# Block_UART_I2C_CAN_and_GPIOs.net
KiCad netlist of a schematic drawn in Altium Designer
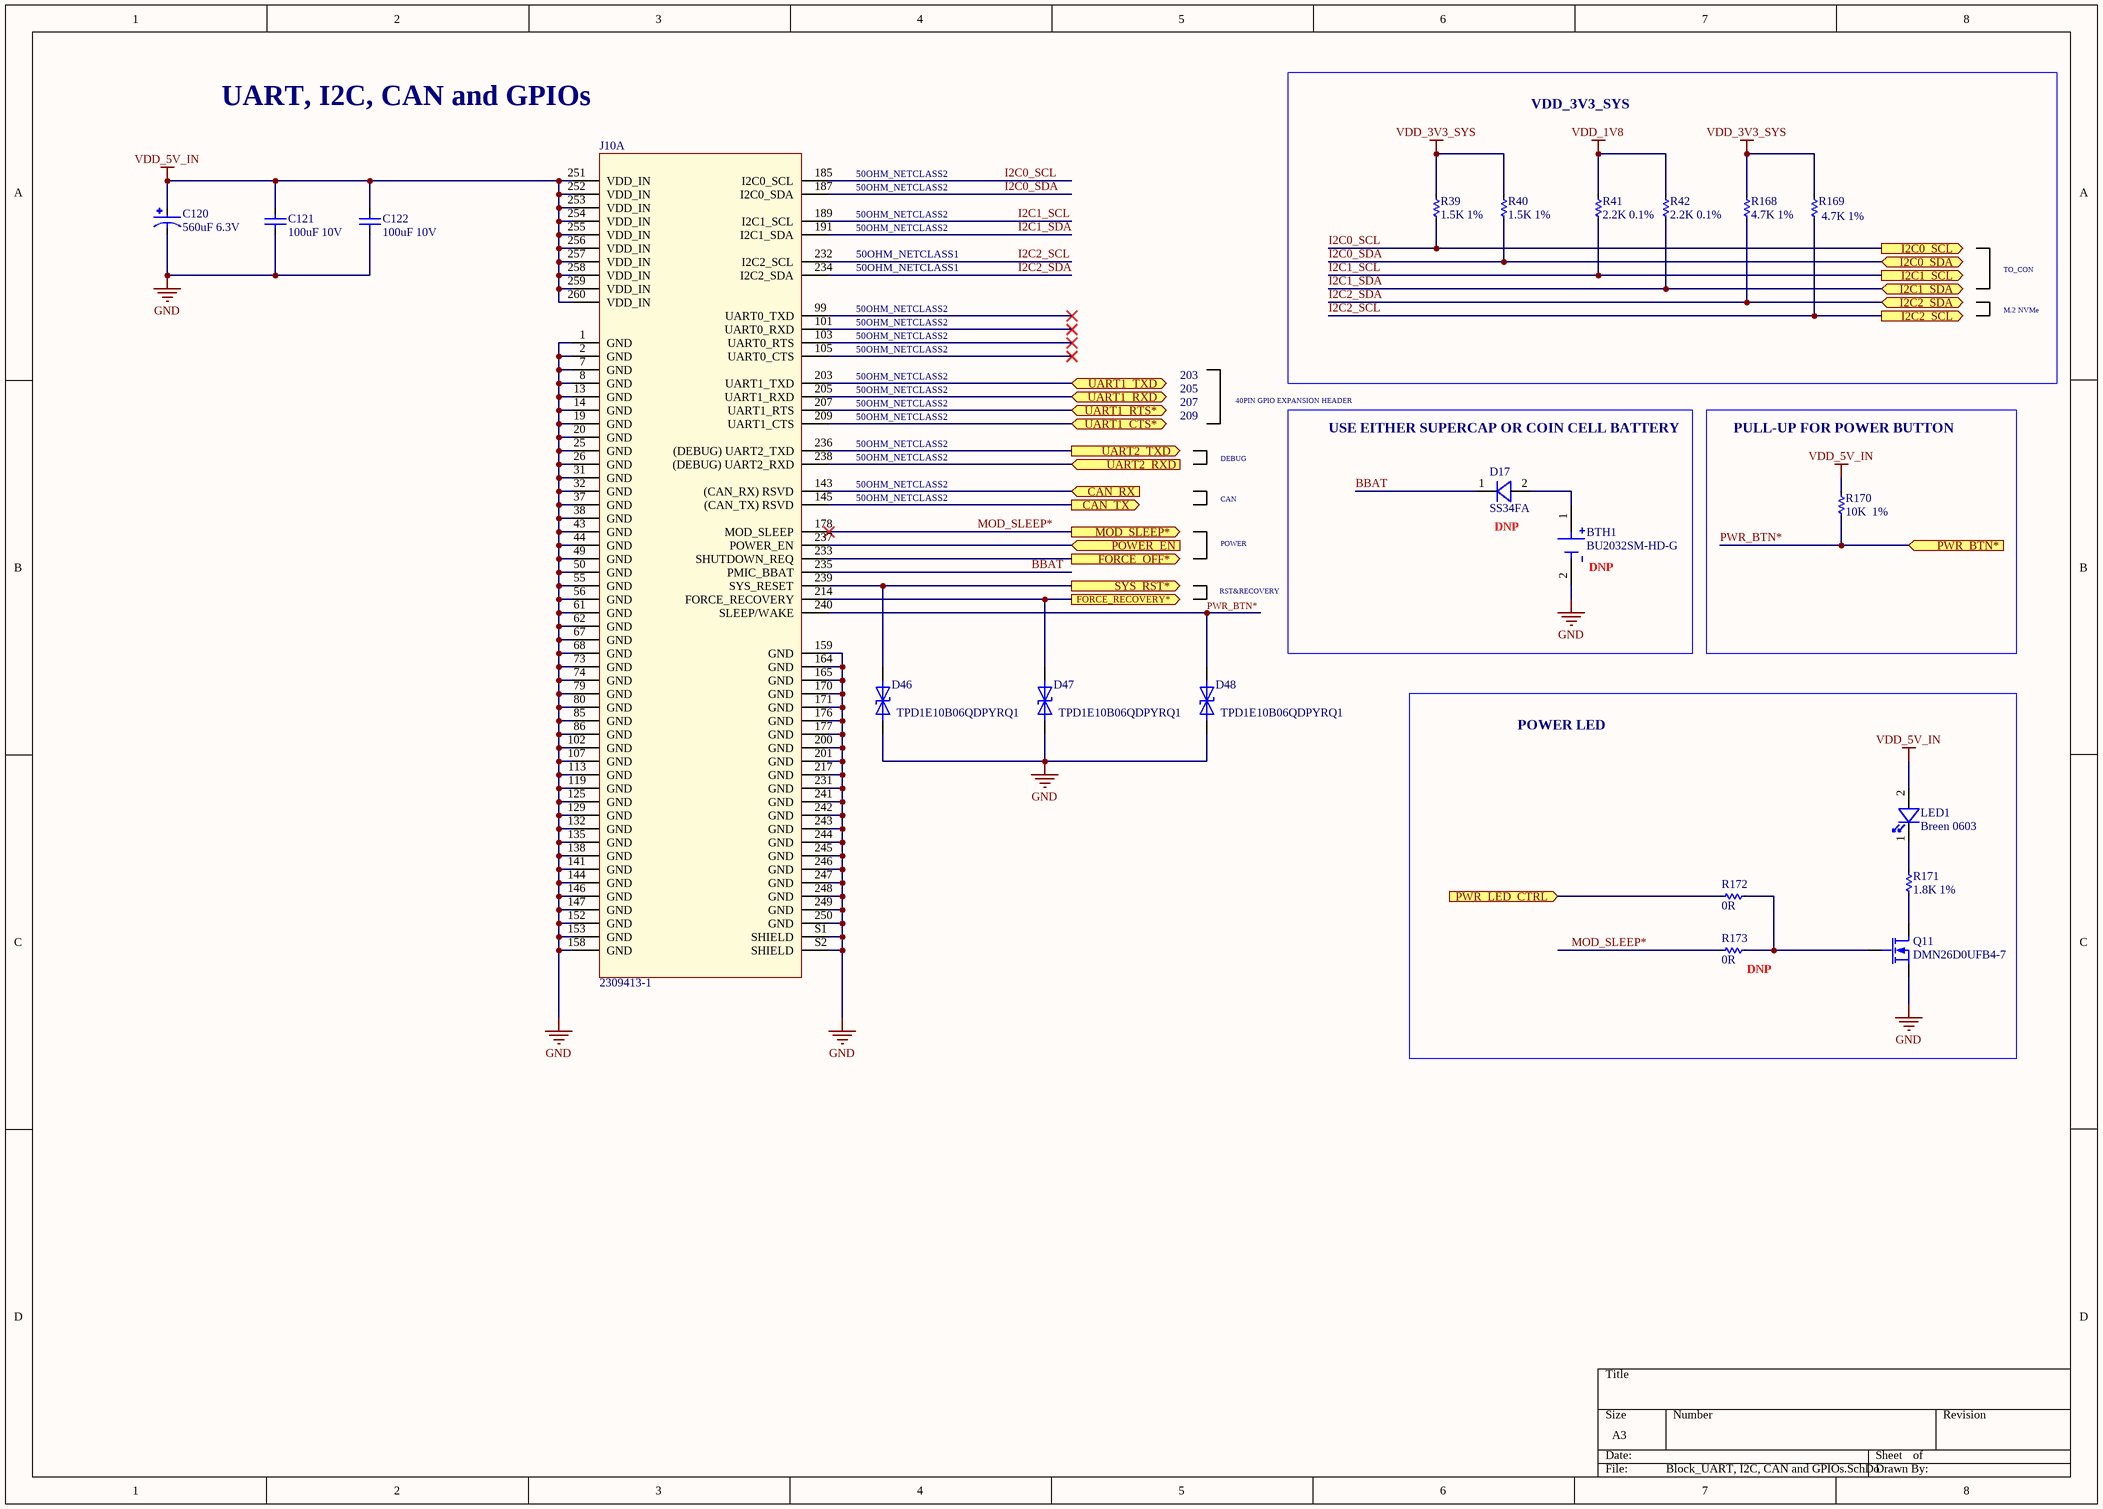
[diagram p0: Block_UART, I2C, CAN and GPIOs.SchDoc]

(export (version "E")
  (design (tool "Eeschema 10.0.6"))
  (components
    (comp (ref "BTH1")
      (value "BU2032SM-HD-G")
      (footprint "BU2032SM-HD-G")
      (description "CR2032 socket on T & R (40")
      (fields (field (name "MANUFACTURER") "Memory Protection Devices"))
      (libsource (lib "GM_Altium_Library") (part "BU2032SM-HD-G"))
    )
    (comp (ref "C120")
      (value "560uF 6.3V")
      (footprint "CP_ELEC_8X7.7")
      (description "Cap Aluminum Polymer 560uF 6.3VDC 20% (8 X 7.7mm) SMD 0.009 Ohm 4500mA 2000h 105C T/R")
      (fields
        (field (name "MANUFACTURER") "Nichicon")
        (field (name "MANUFACTURER PART NUMBER") "RHA0J561MCN1GS")
      )
      (libsource (lib "GM_Altium_Library") (part "RHA0J561MCN1GS"))
    )
    (comp (ref "C121")
      (value "100uF 10V")
      (footprint "C1210")
      (description "Multilayer Ceramic Capacitors (High dielectric type), 10V, 100 uF, ± 20 %, 1210, X5R, RoHS")
      (fields
        (field (name "MANUFACTURER") "Taiyo Yuden")
        (field (name "MANUFACTURER PART NUMBER") "LMK325ABJ107MM-P")
      )
      (libsource (lib "GM_Altium_Library") (part "LMK325ABJ107MM-P"))
    )
    (comp (ref "C122")
      (value "100uF 10V")
      (footprint "C1210")
      (description "Multilayer Ceramic Capacitors (High dielectric type), 10V, 100 uF, ± 20 %, 1210, X5R, RoHS")
      (fields
        (field (name "MANUFACTURER") "Taiyo Yuden")
        (field (name "MANUFACTURER PART NUMBER") "LMK325ABJ107MM-P")
      )
      (libsource (lib "GM_Altium_Library") (part "LMK325ABJ107MM-P"))
    )
    (comp (ref "D17")
      (value "SS34FA")
      (footprint "SOD123F")
      (description "SS34FA Series 40 V 3 A Surface Mount Schottky Barrier Rectifier - SOD-123FA")
      (fields (field (name "MANUFACTURER") "ON Semiconductor / Fairchild"))
      (libsource (lib "GM_Altium_Library") (part "SS34FA"))
    )
    (comp (ref "D46")
      (value "TPD1E10B06QDPYRQ1")
      (footprint "2-X1SON (1x.60)")
      (description "Automotive 12-pF, ±5.5V ±30-kV ESD protection diode in 0402 Package 2-X1SON -40 to 125")
      (fields (field (name "MANUFACTURER") "Texas Instruments"))
      (libsource (lib "GM_Altium_Library") (part "TPD1E10B06QDPYRQ1"))
    )
    (comp (ref "D47")
      (value "TPD1E10B06QDPYRQ1")
      (footprint "2-X1SON (1x.60)")
      (description "Automotive 12-pF, ±5.5V ±30-kV ESD protection diode in 0402 Package 2-X1SON -40 to 125")
      (fields (field (name "MANUFACTURER") "Texas Instruments"))
      (libsource (lib "GM_Altium_Library") (part "TPD1E10B06QDPYRQ1"))
    )
    (comp (ref "D48")
      (value "TPD1E10B06QDPYRQ1")
      (footprint "2-X1SON (1x.60)")
      (description "Automotive 12-pF, ±5.5V ±30-kV ESD protection diode in 0402 Package 2-X1SON -40 to 125")
      (fields (field (name "MANUFACTURER") "Texas Instruments"))
      (libsource (lib "GM_Altium_Library") (part "TPD1E10B06QDPYRQ1"))
    )
    (comp (ref "J10")
      (value "2309413-1")
      (footprint "2309413-1")
      (description "Conn DDR4 DIMM Socket SKT 260 POS 0.5mm Solder RA SMD T/R")
      (fields (field (name "MANUFACTURER") "TE Connectivity"))
      (libsource (lib "GM_Altium_Library") (part "2309413-1"))
    )
    (comp (ref "LED1")
      (value "Breen 0603")
      (footprint "LED_0603")
      (description "LED Uni-Color Green 565nm 2-Pin Chip LED T/R")
      (fields
        (field (name "MANUFACTURER") "Vishay Lite-On")
        (field (name "MANUFACTURER PART NUMBER") "LTST-C190GKT")
      )
      (libsource (lib "GM_Altium_Library") (part "LTST-C190GKT"))
    )
    (comp (ref "Q11")
      (value "DMN26D0UFB4-7")
      (footprint "DFN1006-3")
      (description "Single N-Channel 20 V 350 mW Silicon Surface Mount Mosfet - DFN-3")
      (fields (field (name "MANUFACTURER") "Diodes"))
      (libsource (lib "GM_Altium_Library") (part "DMN26D0UFB4-7"))
    )
    (comp (ref "R39")
      (value "1.5K 1%")
      (footprint "R0402")
      (description "RES SMD 1.5K OHM 1% 1/16W 0402")
      (fields
        (field (name "MANUFACTURER") "Yageo")
        (field (name "MANUFACTURER PART NUMBER") "RC0402FR-071K5L")
      )
      (libsource (lib "GM_Altium_Library") (part "RC0402FR-071K5L"))
    )
    (comp (ref "R40")
      (value "1.5K 1%")
      (footprint "R0402")
      (description "RES SMD 1.5K OHM 1% 1/16W 0402")
      (fields
        (field (name "MANUFACTURER") "Yageo")
        (field (name "MANUFACTURER PART NUMBER") "RC0402FR-071K5L")
      )
      (libsource (lib "GM_Altium_Library") (part "RC0402FR-071K5L"))
    )
    (comp (ref "R41")
      (value "2.2K 0.1%")
      (footprint "R0603")
      (description "Res Thin Film 0603 2.2K Ohm 0.1% 1/16W ±25ppm/°C Molded SMD SMD Paper T/R")
      (fields
        (field (name "MANUFACTURER") "TE Connectivity Neohm")
        (field (name "MANUFACTURER PART NUMBER") "CPF0603B2K2E1")
      )
      (libsource (lib "GM_Altium_Library") (part "CPF0603B2K2E1"))
    )
    (comp (ref "R42")
      (value "2.2K 0.1%")
      (footprint "R0603")
      (description "Res Thin Film 0603 2.2K Ohm 0.1% 1/16W ±25ppm/°C Molded SMD SMD Paper T/R")
      (fields
        (field (name "MANUFACTURER") "TE Connectivity Neohm")
        (field (name "MANUFACTURER PART NUMBER") "CPF0603B2K2E1")
      )
      (libsource (lib "GM_Altium_Library") (part "CPF0603B2K2E1"))
    )
    (comp (ref "R168")
      (value "4.7K 1%")
      (footprint "R0402")
      (description "YAGEO (PHYCOMP) - RC0402FR-074K7L - RES, THICK FILM, 4K7, 1%, 0.063W, 0402")
      (fields
        (field (name "MANUFACTURER") "Yageo")
        (field (name "MANUFACTURER PART NUMBER") "RC0402FR-074K7L")
      )
      (libsource (lib "GM_Altium_Library") (part "RC0402FR-074K7L"))
    )
    (comp (ref "R169")
      (value "4.7K 1%")
      (footprint "R0402")
      (description "YAGEO (PHYCOMP) - RC0402FR-074K7L - RES, THICK FILM, 4K7, 1%, 0.063W, 0402")
      (fields
        (field (name "MANUFACTURER") "Yageo")
        (field (name "MANUFACTURER PART NUMBER") "RC0402FR-074K7L")
      )
      (libsource (lib "GM_Altium_Library") (part "RC0402FR-074K7L"))
    )
    (comp (ref "R170")
      (value "10K  1%")
      (footprint "R0402")
      (description "Res General Purpose Thick Film 0402 10K Ohm 1% 1/16W ±100ppm/°C Molded SMD Paper T/R")
      (fields
        (field (name "MANUFACTURER") "Yageo")
        (field (name "MANUFACTURER PART NUMBER") "RC0402FR-0710KP")
      )
      (libsource (lib "GM_Altium_Library") (part "RC0402FR-0710KP"))
    )
    (comp (ref "R171")
      (value "1.8K 1%")
      (footprint "R0402")
      (description "Res General Purpose Thick Film 0402 1.8K Ohm 1% 1/16W ±100ppm/°C Molded SMD Paper T/R")
      (fields
        (field (name "MANUFACTURER") "Yageo")
        (field (name "MANUFACTURER PART NUMBER") "RC0402FR-071K8L")
      )
      (libsource (lib "GM_Altium_Library") (part "RC0402FR-071K8L"))
    )
    (comp (ref "R172")
      (value "0R")
      (footprint "R0603")
      (description "RES SMD 0 OHM JUMPER 1/10W 0603")
      (fields
        (field (name "MANUFACTURER") "Bourns")
        (field (name "MANUFACTURER PART NUMBER") "CR0603-J/-000ELF")
      )
      (libsource (lib "GM_Altium_Library") (part "CR0603-J/-000ELF"))
    )
    (comp (ref "R173")
      (value "0R")
      (footprint "R0603")
      (description "RES SMD 0 OHM JUMPER 1/10W 0603")
      (fields
        (field (name "MANUFACTURER") "Bourns")
        (field (name "MANUFACTURER PART NUMBER") "CR0603-J/-000ELF")
      )
      (libsource (lib "GM_Altium_Library") (part "CR0603-J/-000ELF"))
    )
  )
  (nets
    (net (code "1") (name "/BBAT") (class "Default")
      (node (ref "D17") (pin "1") (pinfunction "K_1") (pintype "passive"))
      (node (ref "J10") (pin "235") (pinfunction "PMIC_BBAT_235") (pintype "passive"))
    )
    (net (code "2") (name "/CAN_RX") (class "Default")
      (node (ref "J10") (pin "143") (pinfunction "(CAN_RX)_RSVD_143") (pintype "passive"))
    )
    (net (code "3") (name "/CAN_TX") (class "Default")
      (node (ref "J10") (pin "145") (pinfunction "(CAN_TX)_RSVD_145") (pintype "passive"))
    )
    (net (code "4") (name "/FORCE_OFF*") (class "Default")
      (node (ref "J10") (pin "233") (pinfunction "SHUTDOWN_REQ_233") (pintype "passive"))
    )
    (net (code "5") (name "/FORCE_RECOVERY*") (class "Default")
      (node (ref "D47") (pin "2") (pinfunction "2_2") (pintype "passive"))
      (node (ref "J10") (pin "214") (pinfunction "FORCE_RECOVERY_214") (pintype "passive"))
    )
    (net (code "6") (name "/I2C0_SCL") (class "Default")
      (node (ref "J10") (pin "185") (pinfunction "I2C0_SCL_185") (pintype "passive"))
      (node (ref "R39") (pin "1") (pinfunction "1_1") (pintype "passive"))
    )
    (net (code "7") (name "/I2C0_SDA") (class "Default")
      (node (ref "J10") (pin "187") (pinfunction "I2C0_SDA_187") (pintype "passive"))
      (node (ref "R40") (pin "1") (pinfunction "1_1") (pintype "passive"))
    )
    (net (code "8") (name "/I2C1_SCL") (class "Default")
      (node (ref "J10") (pin "189") (pinfunction "I2C1_SCL_189") (pintype "passive"))
      (node (ref "R41") (pin "1") (pinfunction "1_1") (pintype "passive"))
    )
    (net (code "9") (name "/I2C1_SDA") (class "Default")
      (node (ref "J10") (pin "191") (pinfunction "I2C1_SDA_191") (pintype "passive"))
      (node (ref "R42") (pin "1") (pinfunction "1_1") (pintype "passive"))
    )
    (net (code "10") (name "/I2C2_SCL") (class "Default")
      (node (ref "J10") (pin "232") (pinfunction "I2C2_SCL_232") (pintype "passive"))
      (node (ref "R169") (pin "1") (pinfunction "1_1") (pintype "passive"))
    )
    (net (code "11") (name "/I2C2_SDA") (class "Default")
      (node (ref "J10") (pin "234") (pinfunction "I2C2_SDA_234") (pintype "passive"))
      (node (ref "R168") (pin "1") (pinfunction "1_1") (pintype "passive"))
    )
    (net (code "12") (name "/MOD_SLEEP*") (class "Default")
      (node (ref "J10") (pin "178") (pinfunction "MOD_SLEEP_178") (pintype "passive"))
      (node (ref "R173") (pin "1") (pinfunction "1_1") (pintype "passive"))
    )
    (net (code "13") (name "/POWER_EN") (class "Default")
      (node (ref "J10") (pin "237") (pinfunction "POWER_EN_237") (pintype "passive"))
    )
    (net (code "14") (name "/PWR_BTN*") (class "Default")
      (node (ref "D48") (pin "2") (pinfunction "2_2") (pintype "passive"))
      (node (ref "J10") (pin "240") (pinfunction "SLEEP/WAKE_240") (pintype "passive"))
      (node (ref "R170") (pin "1") (pinfunction "1_1") (pintype "passive"))
    )
    (net (code "15") (name "/PWR_LED_CTRL") (class "Default")
      (node (ref "R172") (pin "1") (pinfunction "1_1") (pintype "passive"))
    )
    (net (code "16") (name "/SYS_RST*") (class "Default")
      (node (ref "D46") (pin "2") (pinfunction "2_2") (pintype "passive"))
      (node (ref "J10") (pin "239") (pinfunction "SYS_RESET_239") (pintype "passive"))
    )
    (net (code "17") (name "/UART1_CTS*") (class "Default")
      (node (ref "J10") (pin "209") (pinfunction "UART1_CTS_209") (pintype "passive"))
    )
    (net (code "18") (name "/UART1_RTS*") (class "Default")
      (node (ref "J10") (pin "207") (pinfunction "UART1_RTS_207") (pintype "passive"))
    )
    (net (code "19") (name "/UART1_RXD") (class "Default")
      (node (ref "J10") (pin "205") (pinfunction "UART1_RXD_205") (pintype "passive"))
    )
    (net (code "20") (name "/UART1_TXD") (class "Default")
      (node (ref "J10") (pin "203") (pinfunction "UART1_TXD_203") (pintype "passive"))
    )
    (net (code "21") (name "/UART2_RXD") (class "Default")
      (node (ref "J10") (pin "238") (pinfunction "(DEBUG)_UART2_RXD_238") (pintype "passive"))
    )
    (net (code "22") (name "/UART2_TXD") (class "Default")
      (node (ref "J10") (pin "236") (pinfunction "(DEBUG)_UART2_TXD_236") (pintype "passive"))
    )
    (net (code "23") (name "GND") (class "Default")
      (node (ref "BTH1") (pin "2") (pinfunction "NEG_2") (pintype "passive"))
      (node (ref "C120") (pin "2") (pinfunction "C_2") (pintype "passive"))
      (node (ref "C121") (pin "1") (pinfunction "1_1") (pintype "passive"))
      (node (ref "C122") (pin "1") (pinfunction "1_1") (pintype "passive"))
      (node (ref "D46") (pin "1") (pinfunction "1_1") (pintype "passive"))
      (node (ref "D47") (pin "1") (pinfunction "1_1") (pintype "passive"))
      (node (ref "D48") (pin "1") (pinfunction "1_1") (pintype "passive"))
      (node (ref "J10") (pin "1") (pinfunction "GND_1") (pintype "passive"))
      (node (ref "J10") (pin "102") (pinfunction "GND_102") (pintype "passive"))
      (node (ref "J10") (pin "107") (pinfunction "GND_107") (pintype "passive"))
      (node (ref "J10") (pin "113") (pinfunction "GND_113") (pintype "passive"))
      (node (ref "J10") (pin "119") (pinfunction "GND_119") (pintype "passive"))
      (node (ref "J10") (pin "125") (pinfunction "GND_125") (pintype "passive"))
      (node (ref "J10") (pin "129") (pinfunction "GND_129") (pintype "passive"))
      (node (ref "J10") (pin "13") (pinfunction "GND_13") (pintype "passive"))
      (node (ref "J10") (pin "132") (pinfunction "GND_132") (pintype "passive"))
      (node (ref "J10") (pin "135") (pinfunction "GND_135") (pintype "passive"))
      (node (ref "J10") (pin "138") (pinfunction "GND_138") (pintype "passive"))
      (node (ref "J10") (pin "14") (pinfunction "GND_14") (pintype "passive"))
      (node (ref "J10") (pin "141") (pinfunction "GND_141") (pintype "passive"))
      (node (ref "J10") (pin "144") (pinfunction "GND_144") (pintype "passive"))
      (node (ref "J10") (pin "146") (pinfunction "GND_146") (pintype "passive"))
      (node (ref "J10") (pin "147") (pinfunction "GND_147") (pintype "passive"))
      (node (ref "J10") (pin "152") (pinfunction "GND_152") (pintype "passive"))
      (node (ref "J10") (pin "153") (pinfunction "GND_153") (pintype "passive"))
      (node (ref "J10") (pin "158") (pinfunction "GND_158") (pintype "passive"))
      (node (ref "J10") (pin "159") (pinfunction "GND_159") (pintype "passive"))
      (node (ref "J10") (pin "164") (pinfunction "GND_164") (pintype "passive"))
      (node (ref "J10") (pin "165") (pinfunction "GND_165") (pintype "passive"))
      (node (ref "J10") (pin "170") (pinfunction "GND_170") (pintype "passive"))
      (node (ref "J10") (pin "171") (pinfunction "GND_171") (pintype "passive"))
      (node (ref "J10") (pin "176") (pinfunction "GND_176") (pintype "passive"))
      (node (ref "J10") (pin "177") (pinfunction "GND_177") (pintype "passive"))
      (node (ref "J10") (pin "19") (pinfunction "GND_19") (pintype "passive"))
      (node (ref "J10") (pin "2") (pinfunction "GND_2") (pintype "passive"))
      (node (ref "J10") (pin "20") (pinfunction "GND_20") (pintype "passive"))
      (node (ref "J10") (pin "200") (pinfunction "GND_200") (pintype "passive"))
      (node (ref "J10") (pin "201") (pinfunction "GND_201") (pintype "passive"))
      (node (ref "J10") (pin "217") (pinfunction "GND_217") (pintype "passive"))
      (node (ref "J10") (pin "231") (pinfunction "GND_231") (pintype "passive"))
      (node (ref "J10") (pin "241") (pinfunction "GND_241") (pintype "passive"))
      (node (ref "J10") (pin "242") (pinfunction "GND_242") (pintype "passive"))
      (node (ref "J10") (pin "243") (pinfunction "GND_243") (pintype "passive"))
      (node (ref "J10") (pin "244") (pinfunction "GND_244") (pintype "passive"))
      (node (ref "J10") (pin "245") (pinfunction "GND_245") (pintype "passive"))
      (node (ref "J10") (pin "246") (pinfunction "GND_246") (pintype "passive"))
      (node (ref "J10") (pin "247") (pinfunction "GND_247") (pintype "passive"))
      (node (ref "J10") (pin "248") (pinfunction "GND_248") (pintype "passive"))
      (node (ref "J10") (pin "249") (pinfunction "GND_249") (pintype "passive"))
      (node (ref "J10") (pin "25") (pinfunction "GND_25") (pintype "passive"))
      (node (ref "J10") (pin "250") (pinfunction "GND_250") (pintype "passive"))
      (node (ref "J10") (pin "26") (pinfunction "GND_26") (pintype "passive"))
      (node (ref "J10") (pin "31") (pinfunction "GND_31") (pintype "passive"))
      (node (ref "J10") (pin "32") (pinfunction "GND_32") (pintype "passive"))
      (node (ref "J10") (pin "37") (pinfunction "GND_37") (pintype "passive"))
      (node (ref "J10") (pin "38") (pinfunction "GND_38") (pintype "passive"))
      (node (ref "J10") (pin "43") (pinfunction "GND_43") (pintype "passive"))
      (node (ref "J10") (pin "44") (pinfunction "GND_44") (pintype "passive"))
      (node (ref "J10") (pin "49") (pinfunction "GND_49") (pintype "passive"))
      (node (ref "J10") (pin "50") (pinfunction "GND_50") (pintype "passive"))
      (node (ref "J10") (pin "55") (pinfunction "GND_55") (pintype "passive"))
      (node (ref "J10") (pin "56") (pinfunction "GND_56") (pintype "passive"))
      (node (ref "J10") (pin "61") (pinfunction "GND_61") (pintype "passive"))
      (node (ref "J10") (pin "62") (pinfunction "GND_62") (pintype "passive"))
      (node (ref "J10") (pin "67") (pinfunction "GND_67") (pintype "passive"))
      (node (ref "J10") (pin "68") (pinfunction "GND_68") (pintype "passive"))
      (node (ref "J10") (pin "7") (pinfunction "GND_7") (pintype "passive"))
      (node (ref "J10") (pin "73") (pinfunction "GND_73") (pintype "passive"))
      (node (ref "J10") (pin "74") (pinfunction "GND_74") (pintype "passive"))
      (node (ref "J10") (pin "79") (pinfunction "GND_79") (pintype "passive"))
      (node (ref "J10") (pin "8") (pinfunction "GND_8") (pintype "passive"))
      (node (ref "J10") (pin "80") (pinfunction "GND_80") (pintype "passive"))
      (node (ref "J10") (pin "85") (pinfunction "GND_85") (pintype "passive"))
      (node (ref "J10") (pin "86") (pinfunction "GND_86") (pintype "passive"))
      (node (ref "J10") (pin "S1") (pinfunction "SHIELD_S1") (pintype "passive"))
      (node (ref "J10") (pin "S2") (pinfunction "SHIELD_S2") (pintype "passive"))
      (node (ref "Q11") (pin "2") (pinfunction "S_2") (pintype "passive"))
    )
    (net (code "24") (name "Net-(BTH1-POS)") (class "Default")
      (node (ref "BTH1") (pin "1") (pinfunction "POS_1") (pintype "passive"))
      (node (ref "D17") (pin "2") (pinfunction "A_2") (pintype "passive"))
    )
    (net (code "25") (name "Net-(LED1-K)") (class "Default")
      (node (ref "LED1") (pin "1") (pinfunction "K_1") (pintype "passive"))
      (node (ref "R171") (pin "2") (pinfunction "2_2") (pintype "passive"))
    )
    (net (code "26") (name "Net-(Q11-D)") (class "Default")
      (node (ref "Q11") (pin "3") (pinfunction "D_3") (pintype "passive"))
      (node (ref "R171") (pin "1") (pinfunction "1_1") (pintype "passive"))
    )
    (net (code "27") (name "Net-(Q11-G)") (class "Default")
      (node (ref "Q11") (pin "1") (pinfunction "G_1") (pintype "passive"))
      (node (ref "R172") (pin "2") (pinfunction "2_2") (pintype "passive"))
      (node (ref "R173") (pin "2") (pinfunction "2_2") (pintype "passive"))
    )
    (net (code "28") (name "VDD_1V8") (class "Default")
      (node (ref "R41") (pin "2") (pinfunction "2_2") (pintype "passive"))
      (node (ref "R42") (pin "2") (pinfunction "2_2") (pintype "passive"))
    )
    (net (code "29") (name "VDD_3V3_SYS") (class "Default")
      (node (ref "R168") (pin "2") (pinfunction "2_2") (pintype "passive"))
      (node (ref "R169") (pin "2") (pinfunction "2_2") (pintype "passive"))
      (node (ref "R39") (pin "2") (pinfunction "2_2") (pintype "passive"))
      (node (ref "R40") (pin "2") (pinfunction "2_2") (pintype "passive"))
    )
    (net (code "30") (name "VDD_5V_IN") (class "Default")
      (node (ref "C120") (pin "1") (pinfunction "A_1") (pintype "passive"))
      (node (ref "C121") (pin "2") (pinfunction "2_2") (pintype "passive"))
      (node (ref "C122") (pin "2") (pinfunction "2_2") (pintype "passive"))
      (node (ref "J10") (pin "251") (pinfunction "VDD_IN_251") (pintype "passive"))
      (node (ref "J10") (pin "252") (pinfunction "VDD_IN_252") (pintype "passive"))
      (node (ref "J10") (pin "253") (pinfunction "VDD_IN_253") (pintype "passive"))
      (node (ref "J10") (pin "254") (pinfunction "VDD_IN_254") (pintype "passive"))
      (node (ref "J10") (pin "255") (pinfunction "VDD_IN_255") (pintype "passive"))
      (node (ref "J10") (pin "256") (pinfunction "VDD_IN_256") (pintype "passive"))
      (node (ref "J10") (pin "257") (pinfunction "VDD_IN_257") (pintype "passive"))
      (node (ref "J10") (pin "258") (pinfunction "VDD_IN_258") (pintype "passive"))
      (node (ref "J10") (pin "259") (pinfunction "VDD_IN_259") (pintype "passive"))
      (node (ref "J10") (pin "260") (pinfunction "VDD_IN_260") (pintype "passive"))
      (node (ref "LED1") (pin "2") (pinfunction "A_2") (pintype "passive"))
      (node (ref "R170") (pin "2") (pinfunction "2_2") (pintype "passive"))
    )
    (net (code "31") (name "unconnected-(J10A-UART0_CTS-Pad105)") (class "Default")
      (node (ref "J10") (pin "105") (pinfunction "UART0_CTS_105") (pintype "passive+no_connect"))
    )
    (net (code "32") (name "unconnected-(J10A-UART0_RTS-Pad103)") (class "Default")
      (node (ref "J10") (pin "103") (pinfunction "UART0_RTS_103") (pintype "passive+no_connect"))
    )
    (net (code "33") (name "unconnected-(J10A-UART0_RXD-Pad101)") (class "Default")
      (node (ref "J10") (pin "101") (pinfunction "UART0_RXD_101") (pintype "passive+no_connect"))
    )
    (net (code "34") (name "unconnected-(J10A-UART0_TXD-Pad99)") (class "Default")
      (node (ref "J10") (pin "99") (pinfunction "UART0_TXD_99") (pintype "passive+no_connect"))
    )
  )
)
